# OK1050-C_V1_2_NET.net
KiCad netlist of a schematic drawn in Altium Designer
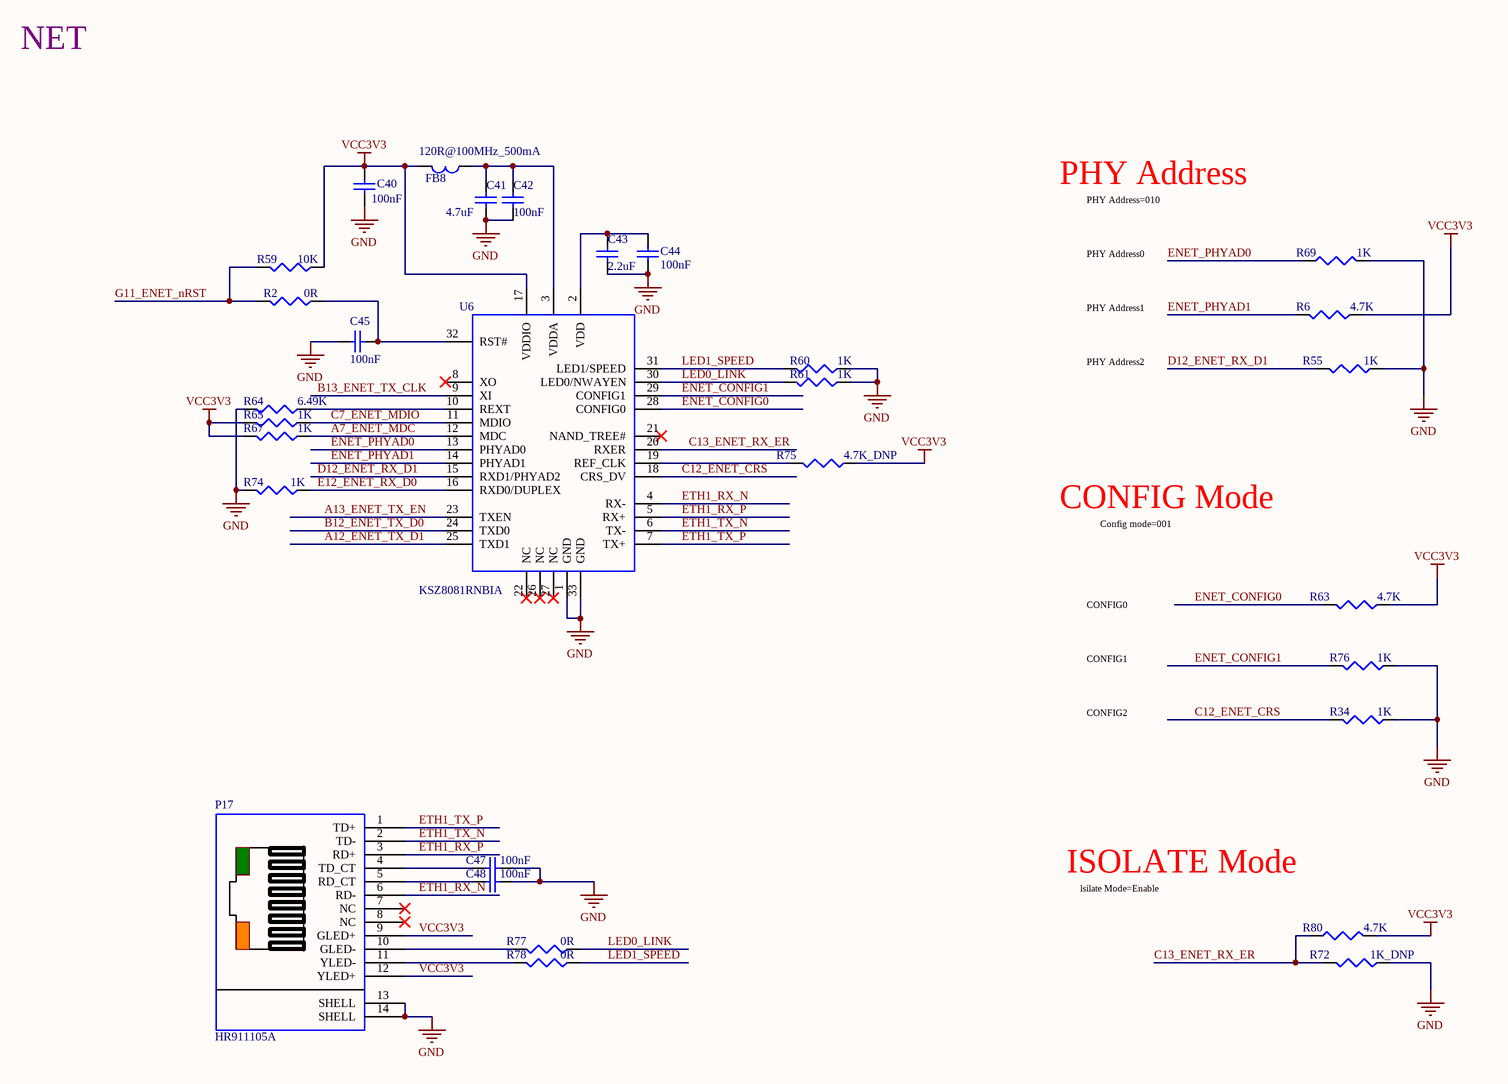
[diagram p0: OK1050-C_V1.2_NET.SchDoc]

(export (version "E")
  (design (tool "Eeschema 10.0.6"))
  (components
    (comp (ref "C40")
      (value "100nF")
      (footprint "0603C+")
      (description "Capacitor")
      (fields (field (name "PUBLISHER") "Altium Limited"))
      (libsource (lib "Miscellaneous Devices") (part "Cap"))
    )
    (comp (ref "C41")
      (value "4.7uF")
      (footprint "0603C+")
      (description "Capacitor")
      (fields (field (name "PUBLISHER") "Altium Limited"))
      (libsource (lib "Miscellaneous Devices") (part "Cap"))
    )
    (comp (ref "C42")
      (value "100nF")
      (footprint "0603C+")
      (description "Capacitor")
      (fields (field (name "PUBLISHER") "Altium Limited"))
      (libsource (lib "Miscellaneous Devices") (part "Cap"))
    )
    (comp (ref "C43")
      (value "2.2uF")
      (footprint "0603C+")
      (description "Capacitor")
      (fields (field (name "PUBLISHER") "Altium Limited"))
      (libsource (lib "Miscellaneous Devices") (part "Cap"))
    )
    (comp (ref "C44")
      (value "100nF")
      (footprint "0603C+")
      (description "Capacitor")
      (fields (field (name "PUBLISHER") "Altium Limited"))
      (libsource (lib "Miscellaneous Devices") (part "Cap"))
    )
    (comp (ref "C45")
      (value "100nF")
      (footprint "0603C+")
      (description "Capacitor")
      (fields (field (name "PUBLISHER") "Altium Limited"))
      (libsource (lib "Miscellaneous Devices") (part "Cap"))
    )
    (comp (ref "C47")
      (value "100nF")
      (footprint "0603C+")
      (description "Capacitor")
      (fields (field (name "PUBLISHER") "Altium Limited"))
      (libsource (lib "Miscellaneous Devices") (part "Cap"))
    )
    (comp (ref "C48")
      (value "100nF")
      (footprint "0603C+")
      (description "Capacitor")
      (fields (field (name "PUBLISHER") "Altium Limited"))
      (libsource (lib "Miscellaneous Devices") (part "Cap"))
    )
    (comp (ref "FB8")
      (value "120R@100MHz_500mA")
      (footprint "0603R+")
      (description "Inductor")
      (fields (field (name "PUBLISHER") "120R@100MHz_500mA"))
      (libsource (lib "Schlib_UL") (part "CZ"))
    )
    (comp (ref "P17")
      (value "HR911105A")
      (footprint "RJ-45A12")
      (libsource (lib "PCB_RT1052") (part "HR911105A"))
    )
    (comp (ref "R2")
      (value "0R")
      (footprint "0603R+")
      (description "Resistor")
      (fields (field (name "PUBLISHER") "Altium Limited"))
      (libsource (lib "Miscellaneous Devices") (part "Res3"))
    )
    (comp (ref "R6")
      (value "4.7K")
      (footprint "0603R+")
      (description "Resistor")
      (fields (field (name "PUBLISHER") "Altium Limited"))
      (libsource (lib "Miscellaneous Devices") (part "Res3"))
    )
    (comp (ref "R34")
      (value "1K")
      (footprint "0603R+")
      (description "Resistor")
      (fields (field (name "PUBLISHER") "Altium Limited"))
      (libsource (lib "Miscellaneous Devices") (part "Res3"))
    )
    (comp (ref "R55")
      (value "1K")
      (footprint "0603R+")
      (description "Resistor")
      (fields (field (name "PUBLISHER") "Altium Limited"))
      (libsource (lib "Miscellaneous Devices") (part "Res3"))
    )
    (comp (ref "R59")
      (value "10K")
      (footprint "0603R+")
      (description "Resistor")
      (fields (field (name "PUBLISHER") "Altium Limited"))
      (libsource (lib "Miscellaneous Devices") (part "Res3"))
    )
    (comp (ref "R60")
      (value "1K")
      (footprint "0603R+")
      (description "Resistor")
      (fields (field (name "PUBLISHER") "Altium Limited"))
      (libsource (lib "Miscellaneous Devices") (part "Res3"))
    )
    (comp (ref "R61")
      (value "1K")
      (footprint "0603R+")
      (description "Resistor")
      (fields (field (name "PUBLISHER") "Altium Limited"))
      (libsource (lib "Miscellaneous Devices") (part "Res3"))
    )
    (comp (ref "R63")
      (value "4.7K")
      (footprint "0603R+")
      (description "Resistor")
      (fields (field (name "PUBLISHER") "Altium Limited"))
      (libsource (lib "Miscellaneous Devices") (part "Res3"))
    )
    (comp (ref "R64")
      (value "6.49K")
      (footprint "0603R+")
      (description "Resistor")
      (fields (field (name "PUBLISHER") "Altium Limited"))
      (libsource (lib "Miscellaneous Devices") (part "Res3"))
    )
    (comp (ref "R65")
      (value "1K")
      (footprint "0603R+")
      (description "Resistor")
      (fields (field (name "PUBLISHER") "Altium Limited"))
      (libsource (lib "Miscellaneous Devices") (part "Res3"))
    )
    (comp (ref "R67")
      (value "1K")
      (footprint "0603R+")
      (description "Resistor")
      (fields (field (name "PUBLISHER") "Altium Limited"))
      (libsource (lib "Miscellaneous Devices") (part "Res3"))
    )
    (comp (ref "R69")
      (value "1K")
      (footprint "0603R+")
      (description "Resistor")
      (fields (field (name "PUBLISHER") "Altium Limited"))
      (libsource (lib "Miscellaneous Devices") (part "Res3"))
    )
    (comp (ref "R72")
      (value "1K_DNP")
      (footprint "0603R+")
      (description "Resistor")
      (fields (field (name "PUBLISHER") "Altium Limited"))
      (libsource (lib "Miscellaneous Devices") (part "Res3"))
    )
    (comp (ref "R74")
      (value "1K")
      (footprint "0603R+")
      (description "Resistor")
      (fields (field (name "PUBLISHER") "Altium Limited"))
      (libsource (lib "Miscellaneous Devices") (part "Res3"))
    )
    (comp (ref "R75")
      (value "4.7K_DNP")
      (footprint "0603R+")
      (description "Resistor")
      (fields (field (name "PUBLISHER") "Altium Limited"))
      (libsource (lib "Miscellaneous Devices") (part "Res3"))
    )
    (comp (ref "R76")
      (value "1K")
      (footprint "0603R+")
      (description "Resistor")
      (fields (field (name "PUBLISHER") "Altium Limited"))
      (libsource (lib "Miscellaneous Devices") (part "Res3"))
    )
    (comp (ref "R77")
      (value "0R")
      (footprint "0603R+")
      (description "Resistor")
      (fields (field (name "PUBLISHER") "Altium Limited"))
      (libsource (lib "Miscellaneous Devices") (part "Res3"))
    )
    (comp (ref "R78")
      (value "0R")
      (footprint "0603R+")
      (description "Resistor")
      (fields (field (name "PUBLISHER") "Altium Limited"))
      (libsource (lib "Miscellaneous Devices") (part "Res3"))
    )
    (comp (ref "R80")
      (value "4.7K")
      (footprint "0603R+")
      (description "Resistor")
      (fields (field (name "PUBLISHER") "Altium Limited"))
      (libsource (lib "Miscellaneous Devices") (part "Res3"))
    )
    (comp (ref "U6")
      (value "KSZ8081RNBIA")
      (footprint "QFN-32")
      (libsource (lib "PCB_RT1052") (part "KSZ8081RNB"))
    )
  )
  (nets
    (net (code "1") (name "/A7_ENET_MDC") (class "Default")
      (node (ref "R67") (pin "1") (pinfunction "1_1") (pintype "passive"))
      (node (ref "U6") (pin "12") (pinfunction "MDC_12") (pintype "passive"))
    )
    (net (code "2") (name "/A12_ENET_TX_D1") (class "Default")
      (node (ref "U6") (pin "25") (pinfunction "TXD1_25") (pintype "passive"))
    )
    (net (code "3") (name "/A13_ENET_TX_EN") (class "Default")
      (node (ref "U6") (pin "23") (pinfunction "TXEN_23") (pintype "passive"))
    )
    (net (code "4") (name "/B12_ENET_TX_D0") (class "Default")
      (node (ref "U6") (pin "24") (pinfunction "TXD0_24") (pintype "passive"))
    )
    (net (code "5") (name "/B13_ENET_TX_CLK") (class "Default")
      (node (ref "U6") (pin "9") (pinfunction "XI_9") (pintype "passive"))
    )
    (net (code "6") (name "/C7_ENET_MDIO") (class "Default")
      (node (ref "R65") (pin "1") (pinfunction "1_1") (pintype "passive"))
      (node (ref "U6") (pin "11") (pinfunction "MDIO_11") (pintype "passive"))
    )
    (net (code "7") (name "/C12_ENET_CRS") (class "Default")
      (node (ref "R34") (pin "2") (pinfunction "2_2") (pintype "passive"))
      (node (ref "U6") (pin "18") (pinfunction "CRS_DV_18") (pintype "passive"))
    )
    (net (code "8") (name "/C13_ENET_RX_ER") (class "Default")
      (node (ref "R72") (pin "2") (pinfunction "2_2") (pintype "passive"))
      (node (ref "R80") (pin "1") (pinfunction "1_1") (pintype "passive"))
      (node (ref "U6") (pin "20") (pinfunction "RXER_20") (pintype "passive"))
    )
    (net (code "9") (name "/D12_ENET_RX_D1") (class "Default")
      (node (ref "R55") (pin "2") (pinfunction "2_2") (pintype "passive"))
      (node (ref "U6") (pin "15") (pinfunction "RXD1/PHYAD2_15") (pintype "passive"))
    )
    (net (code "10") (name "/E12_ENET_RX_D0") (class "Default")
      (node (ref "R74") (pin "1") (pinfunction "1_1") (pintype "passive"))
      (node (ref "U6") (pin "16") (pinfunction "RXD0/DUPLEX_16") (pintype "passive"))
    )
    (net (code "11") (name "/ENET_CONFIG0") (class "Default")
      (node (ref "R63") (pin "2") (pinfunction "2_2") (pintype "passive"))
      (node (ref "U6") (pin "28") (pinfunction "CONFIG0_28") (pintype "passive"))
    )
    (net (code "12") (name "/ENET_CONFIG1") (class "Default")
      (node (ref "R76") (pin "2") (pinfunction "2_2") (pintype "passive"))
      (node (ref "U6") (pin "29") (pinfunction "CONFIG1_29") (pintype "passive"))
    )
    (net (code "13") (name "/ENET_PHYAD0") (class "Default")
      (node (ref "R69") (pin "1") (pinfunction "1_1") (pintype "passive"))
      (node (ref "U6") (pin "13") (pinfunction "PHYAD0_13") (pintype "passive"))
    )
    (net (code "14") (name "/ENET_PHYAD1") (class "Default")
      (node (ref "R6") (pin "2") (pinfunction "2_2") (pintype "passive"))
      (node (ref "U6") (pin "14") (pinfunction "PHYAD1_14") (pintype "passive"))
    )
    (net (code "15") (name "/ETH1_RX_N") (class "Default")
      (node (ref "P17") (pin "6") (pinfunction "RD-_6") (pintype "passive"))
      (node (ref "U6") (pin "4") (pinfunction "RX-_4") (pintype "passive"))
    )
    (net (code "16") (name "/ETH1_RX_P") (class "Default")
      (node (ref "P17") (pin "3") (pinfunction "RD+_3") (pintype "passive"))
      (node (ref "U6") (pin "5") (pinfunction "RX+_5") (pintype "passive"))
    )
    (net (code "17") (name "/ETH1_TX_N") (class "Default")
      (node (ref "P17") (pin "2") (pinfunction "TD-_2") (pintype "passive"))
      (node (ref "U6") (pin "6") (pinfunction "TX-_6") (pintype "passive"))
    )
    (net (code "18") (name "/ETH1_TX_P") (class "Default")
      (node (ref "P17") (pin "1") (pinfunction "TD+_1") (pintype "passive"))
      (node (ref "U6") (pin "7") (pinfunction "TX+_7") (pintype "passive"))
    )
    (net (code "19") (name "/G11_ENET_nRST") (class "Default")
      (node (ref "R2") (pin "2") (pinfunction "2_2") (pintype "passive"))
      (node (ref "R59") (pin "2") (pinfunction "2_2") (pintype "passive"))
    )
    (net (code "20") (name "/LED0_LINK") (class "Default")
      (node (ref "R61") (pin "2") (pinfunction "2_2") (pintype "passive"))
      (node (ref "R77") (pin "1") (pinfunction "1_1") (pintype "passive"))
      (node (ref "U6") (pin "30") (pinfunction "LED0/NWAYEN_30") (pintype "passive"))
    )
    (net (code "21") (name "/LED1_SPEED") (class "Default")
      (node (ref "R60") (pin "2") (pinfunction "2_2") (pintype "passive"))
      (node (ref "R78") (pin "1") (pinfunction "1_1") (pintype "passive"))
      (node (ref "U6") (pin "31") (pinfunction "LED1/SPEED_31") (pintype "passive"))
    )
    (net (code "22") (name "GND") (class "Default")
      (node (ref "C40") (pin "2") (pinfunction "2_2") (pintype "passive"))
      (node (ref "C41") (pin "2") (pinfunction "2_2") (pintype "passive"))
      (node (ref "C42") (pin "2") (pinfunction "2_2") (pintype "passive"))
      (node (ref "C43") (pin "2") (pinfunction "2_2") (pintype "passive"))
      (node (ref "C44") (pin "2") (pinfunction "2_2") (pintype "passive"))
      (node (ref "C45") (pin "1") (pinfunction "1_1") (pintype "passive"))
      (node (ref "C47") (pin "1") (pinfunction "1_1") (pintype "passive"))
      (node (ref "C48") (pin "1") (pinfunction "1_1") (pintype "passive"))
      (node (ref "P17") (pin "13") (pinfunction "SHELL_13") (pintype "passive"))
      (node (ref "P17") (pin "14") (pinfunction "SHELL_14") (pintype "passive"))
      (node (ref "R34") (pin "1") (pinfunction "1_1") (pintype "passive"))
      (node (ref "R55") (pin "1") (pinfunction "1_1") (pintype "passive"))
      (node (ref "R60") (pin "1") (pinfunction "1_1") (pintype "passive"))
      (node (ref "R61") (pin "1") (pinfunction "1_1") (pintype "passive"))
      (node (ref "R64") (pin "2") (pinfunction "2_2") (pintype "passive"))
      (node (ref "R69") (pin "2") (pinfunction "2_2") (pintype "passive"))
      (node (ref "R72") (pin "1") (pinfunction "1_1") (pintype "passive"))
      (node (ref "R74") (pin "2") (pinfunction "2_2") (pintype "passive"))
      (node (ref "R76") (pin "1") (pinfunction "1_1") (pintype "passive"))
      (node (ref "U6") (pin "1") (pinfunction "GND_1") (pintype "passive"))
      (node (ref "U6") (pin "33") (pinfunction "GND_33") (pintype "passive"))
    )
    (net (code "23") (name "Net-(P17-GLED-)") (class "Default")
      (node (ref "P17") (pin "10") (pinfunction "GLED-_10") (pintype "passive"))
      (node (ref "R77") (pin "2") (pinfunction "2_2") (pintype "passive"))
    )
    (net (code "24") (name "Net-(P17-RD_CT)") (class "Default")
      (node (ref "C48") (pin "2") (pinfunction "2_2") (pintype "passive"))
      (node (ref "P17") (pin "5") (pinfunction "RD_CT_5") (pintype "passive"))
    )
    (net (code "25") (name "Net-(P17-TD_CT)") (class "Default")
      (node (ref "C47") (pin "2") (pinfunction "2_2") (pintype "passive"))
      (node (ref "P17") (pin "4") (pinfunction "TD_CT_4") (pintype "passive"))
    )
    (net (code "26") (name "Net-(P17-YLED-)") (class "Default")
      (node (ref "P17") (pin "11") (pinfunction "YLED-_11") (pintype "passive"))
      (node (ref "R78") (pin "2") (pinfunction "2_2") (pintype "passive"))
    )
    (net (code "27") (name "Net-(U6-REF_CLK)") (class "Default")
      (node (ref "R75") (pin "2") (pinfunction "2_2") (pintype "passive"))
      (node (ref "U6") (pin "19") (pinfunction "REF_CLK_19") (pintype "passive"))
    )
    (net (code "28") (name "Net-(U6-REXT)") (class "Default")
      (node (ref "R64") (pin "1") (pinfunction "1_1") (pintype "passive"))
      (node (ref "U6") (pin "10") (pinfunction "REXT_10") (pintype "passive"))
    )
    (net (code "29") (name "Net-(U6-RST#)") (class "Default")
      (node (ref "C45") (pin "2") (pinfunction "2_2") (pintype "passive"))
      (node (ref "R2") (pin "1") (pinfunction "1_1") (pintype "passive"))
      (node (ref "U6") (pin "32") (pinfunction "RST#_32") (pintype "passive"))
    )
    (net (code "30") (name "Net-(U6-VDD)") (class "Default")
      (node (ref "C43") (pin "1") (pinfunction "1_1") (pintype "passive"))
      (node (ref "C44") (pin "1") (pinfunction "1_1") (pintype "passive"))
      (node (ref "U6") (pin "2") (pinfunction "VDD_2") (pintype "passive"))
    )
    (net (code "31") (name "Net-(U6-VDDA)") (class "Default")
      (node (ref "C41") (pin "1") (pinfunction "1_1") (pintype "passive"))
      (node (ref "C42") (pin "1") (pinfunction "1_1") (pintype "passive"))
      (node (ref "FB8") (pin "1") (pinfunction "1_1") (pintype "passive"))
      (node (ref "U6") (pin "3") (pinfunction "VDDA_3") (pintype "passive"))
    )
    (net (code "32") (name "VCC3V3") (class "Default")
      (node (ref "C40") (pin "1") (pinfunction "1_1") (pintype "passive"))
      (node (ref "FB8") (pin "2") (pinfunction "2_2") (pintype "passive"))
      (node (ref "P17") (pin "12") (pinfunction "YLED+_12") (pintype "passive"))
      (node (ref "P17") (pin "9") (pinfunction "GLED+_9") (pintype "passive"))
      (node (ref "R59") (pin "1") (pinfunction "1_1") (pintype "passive"))
      (node (ref "R6") (pin "1") (pinfunction "1_1") (pintype "passive"))
      (node (ref "R63") (pin "1") (pinfunction "1_1") (pintype "passive"))
      (node (ref "R65") (pin "2") (pinfunction "2_2") (pintype "passive"))
      (node (ref "R67") (pin "2") (pinfunction "2_2") (pintype "passive"))
      (node (ref "R75") (pin "1") (pinfunction "1_1") (pintype "passive"))
      (node (ref "R80") (pin "2") (pinfunction "2_2") (pintype "passive"))
      (node (ref "U6") (pin "17") (pinfunction "VDDIO_17") (pintype "passive"))
    )
    (net (code "33") (name "unconnected-(P17-NC-Pad7)") (class "Default")
      (node (ref "P17") (pin "7") (pinfunction "NC_7") (pintype "passive+no_connect"))
    )
    (net (code "34") (name "unconnected-(P17-NC-Pad8)") (class "Default")
      (node (ref "P17") (pin "8") (pinfunction "NC_8") (pintype "passive+no_connect"))
    )
    (net (code "35") (name "unconnected-(U6-NAND_TREE#-Pad21)") (class "Default")
      (node (ref "U6") (pin "21") (pinfunction "NAND_TREE#_21") (pintype "passive+no_connect"))
    )
    (net (code "36") (name "unconnected-(U6-NC-Pad22)") (class "Default")
      (node (ref "U6") (pin "22") (pinfunction "NC_22") (pintype "passive+no_connect"))
    )
    (net (code "37") (name "unconnected-(U6-NC-Pad26)") (class "Default")
      (node (ref "U6") (pin "26") (pinfunction "NC_26") (pintype "passive+no_connect"))
    )
    (net (code "38") (name "unconnected-(U6-NC-Pad27)") (class "Default")
      (node (ref "U6") (pin "27") (pinfunction "NC_27") (pintype "passive+no_connect"))
    )
    (net (code "39") (name "unconnected-(U6-XO-Pad8)") (class "Default")
      (node (ref "U6") (pin "8") (pinfunction "XO_8") (pintype "passive+no_connect"))
    )
  )
)
